# FPGA_0_V1_01.net
KiCad netlist of a schematic drawn in Altium Designer
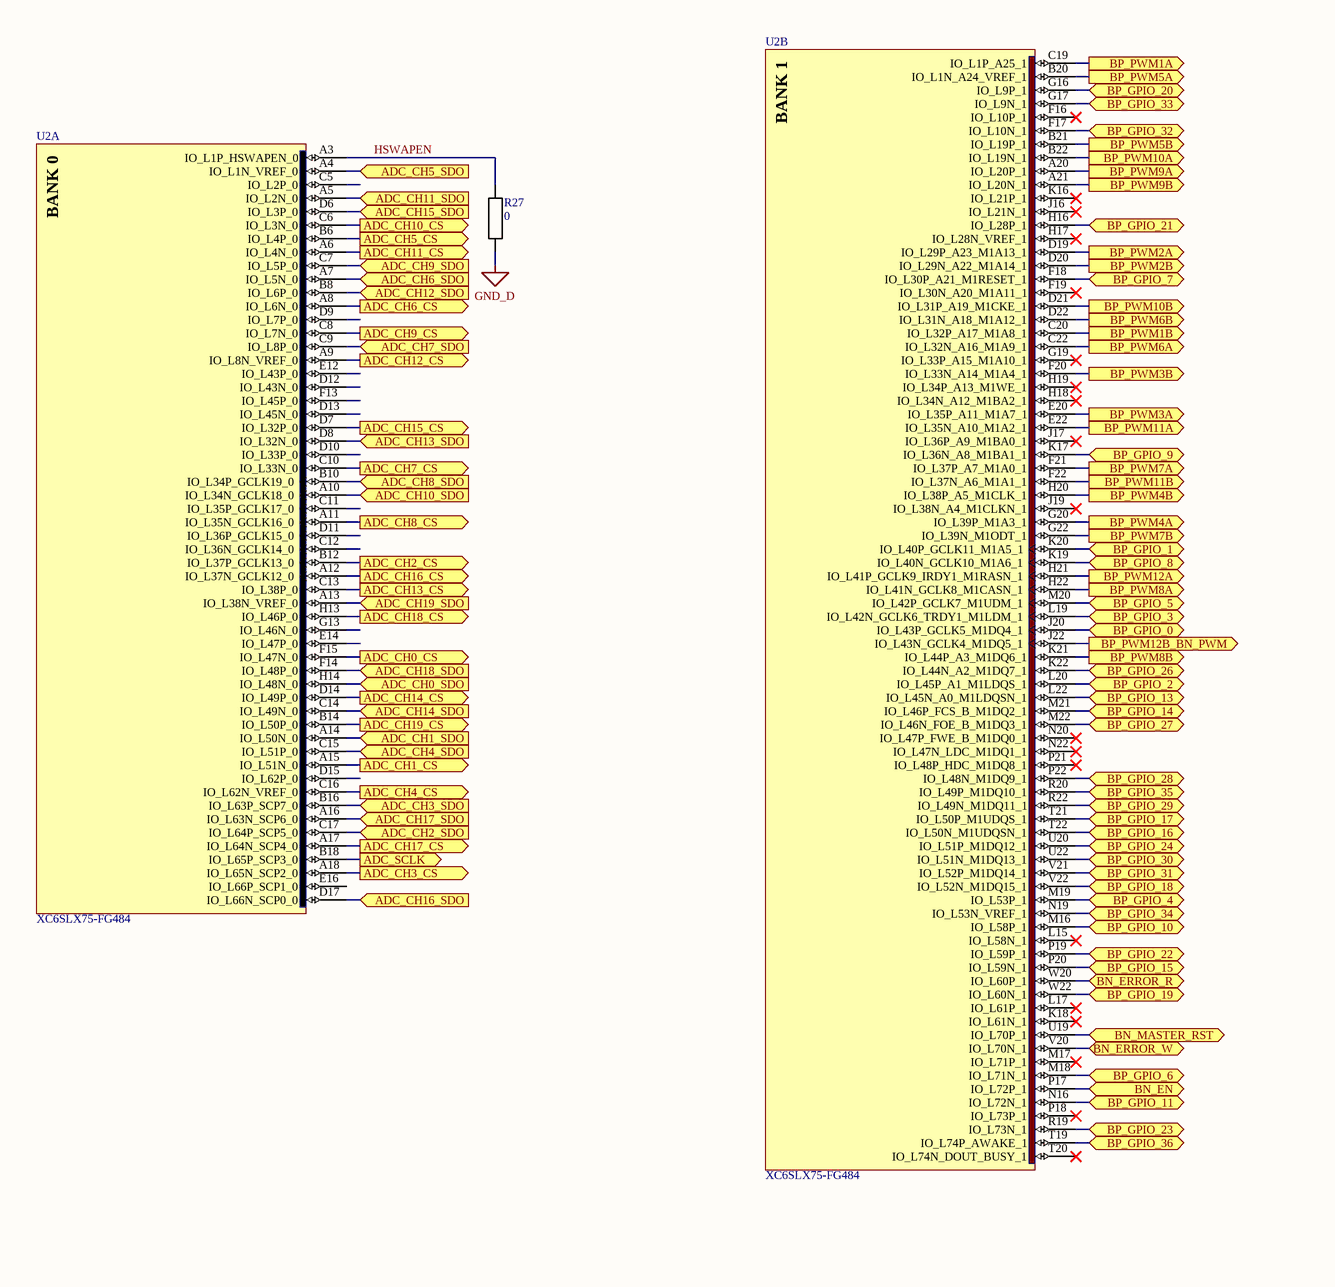
[diagram p0: FPGA_0_V1_01.SchDoc, left]
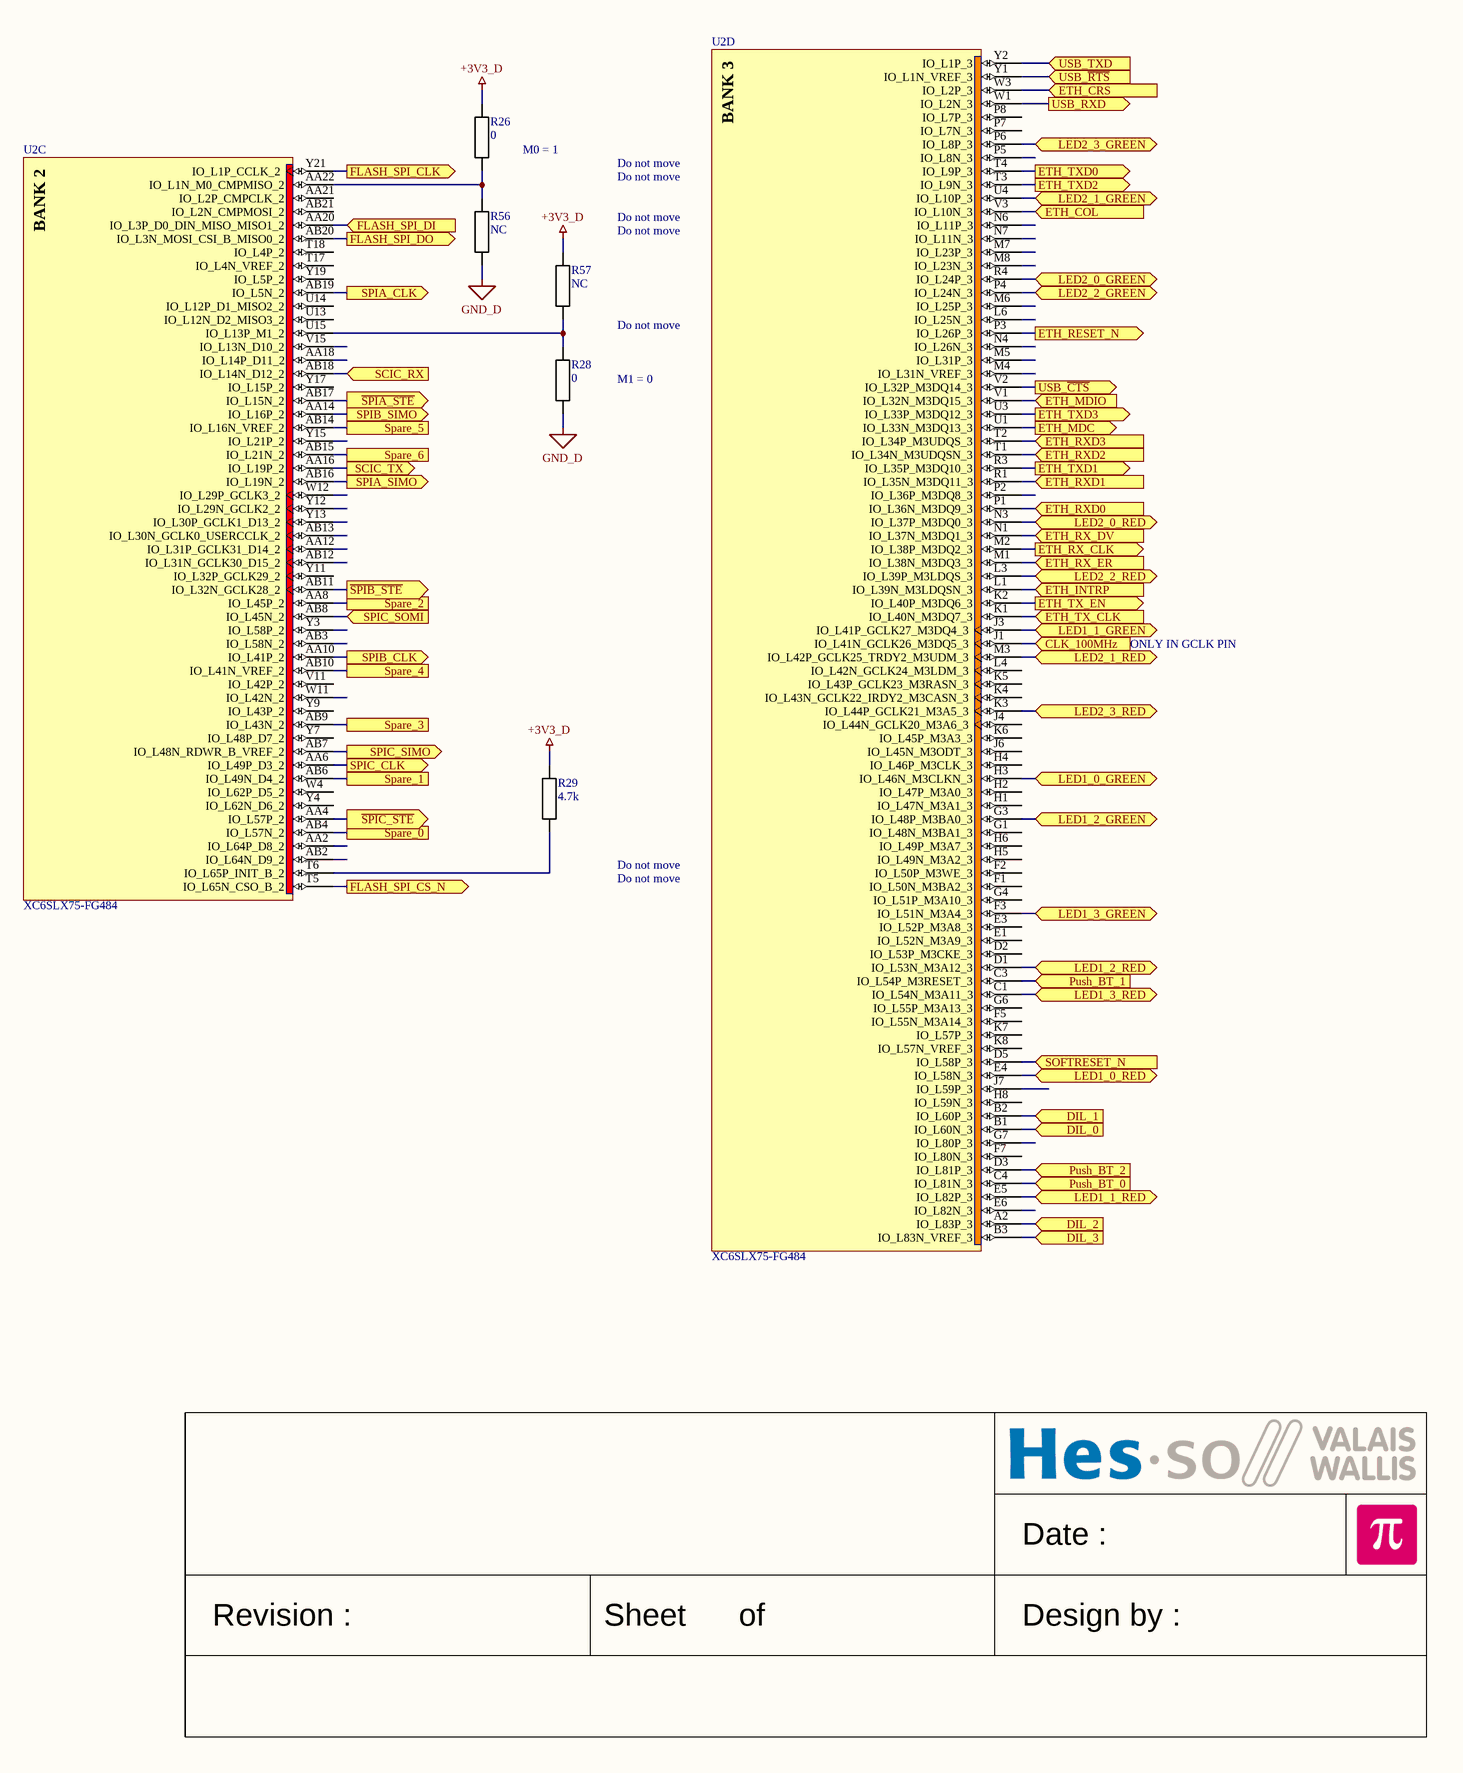
[diagram p1: FPGA_0_V1_01.SchDoc, right]

(export (version "E")
  (design (tool "Eeschema 10.0.6"))
  (components
    (comp (ref "R26")
      (value "0")
      (footprint "RESISTOR 2012 REFLOW")
      (description "Resistor 1% 50V 125mW 2012(0805)")
      (libsource (lib "Resistor") (part "Resistor"))
    )
    (comp (ref "R27")
      (value "0")
      (footprint "RESISTOR 2012 REFLOW")
      (description "Resistor 1% 50V 125mW 2012(0805)")
      (libsource (lib "Resistor") (part "Resistor"))
    )
    (comp (ref "R28")
      (value "0")
      (footprint "RESISTOR 2012 REFLOW")
      (description "Resistor 1% 50V 125mW 2012(0805)")
      (libsource (lib "Resistor") (part "Resistor"))
    )
    (comp (ref "R29")
      (value "4.7k")
      (footprint "RESISTOR 2012 REFLOW")
      (description "Resistor 1% 50V 125mW 2012(0805)")
      (libsource (lib "Resistor") (part "Resistor"))
    )
    (comp (ref "R56")
      (value "NC")
      (footprint "RESISTOR 2012 REFLOW")
      (description "Resistor 1% 50V 125mW 2012(0805)")
      (libsource (lib "Resistor") (part "Resistor"))
    )
    (comp (ref "R57")
      (value "NC")
      (footprint "RESISTOR 2012 REFLOW")
      (description "Resistor 1% 50V 125mW 2012(0805)")
      (libsource (lib "Resistor") (part "Resistor"))
    )
    (comp (ref "U2")
      (value "XC6SLX75-FG484")
      (footprint "BGA484 P1.0 C23X23 H2.2")
      (description "Spartan-6 LXT 1.2V FPGA, 268 User I/Os, 484-Ball Fine-Pitch BGA (1.0mm Pitch)")
      (libsource (lib "Processor") (part "XC6SLX75-FG484"))
    )
  )
  (nets
    (net (code "1") (name "+3V3_D") (class "Default")
      (node (ref "R26") (pin "2") (pinfunction "2_2") (pintype "passive"))
      (node (ref "R29") (pin "2") (pinfunction "2_2") (pintype "passive"))
      (node (ref "R57") (pin "2") (pinfunction "2_2") (pintype "passive"))
    )
    (net (code "2") (name "/ADC_CH0_CS") (class "Default")
      (node (ref "U2") (pin "F15") (pinfunction "IO_L47N_0_F15") (pintype "bidirectional"))
    )
    (net (code "3") (name "/ADC_CH0_SDO") (class "Default")
      (node (ref "U2") (pin "H14") (pinfunction "IO_L48N_0_H14") (pintype "bidirectional"))
    )
    (net (code "4") (name "/ADC_CH1_CS") (class "Default")
      (node (ref "U2") (pin "A15") (pinfunction "IO_L51N_0_A15") (pintype "bidirectional"))
    )
    (net (code "5") (name "/ADC_CH1_SDO") (class "Default")
      (node (ref "U2") (pin "A14") (pinfunction "IO_L50N_0_A14") (pintype "bidirectional"))
    )
    (net (code "6") (name "/ADC_CH2_CS") (class "Default")
      (node (ref "U2") (pin "B12") (pinfunction "IO_L37P_GCLK13_0_B12") (pintype "bidirectional"))
    )
    (net (code "7") (name "/ADC_CH2_SDO") (class "Default")
      (node (ref "U2") (pin "C17") (pinfunction "IO_L64P_SCP5_0_C17") (pintype "bidirectional"))
    )
    (net (code "8") (name "/ADC_CH3_CS") (class "Default")
      (node (ref "U2") (pin "A18") (pinfunction "IO_L65N_SCP2_0_A18") (pintype "bidirectional"))
    )
    (net (code "9") (name "/ADC_CH3_SDO") (class "Default")
      (node (ref "U2") (pin "B16") (pinfunction "IO_L63P_SCP7_0_B16") (pintype "bidirectional"))
    )
    (net (code "10") (name "/ADC_CH4_CS") (class "Default")
      (node (ref "U2") (pin "C16") (pinfunction "IO_L62N_VREF_0_C16") (pintype "bidirectional"))
    )
    (net (code "11") (name "/ADC_CH4_SDO") (class "Default")
      (node (ref "U2") (pin "C15") (pinfunction "IO_L51P_0_C15") (pintype "bidirectional"))
    )
    (net (code "12") (name "/ADC_CH5_CS") (class "Default")
      (node (ref "U2") (pin "B6") (pinfunction "IO_L4P_0_B6") (pintype "bidirectional"))
    )
    (net (code "13") (name "/ADC_CH5_SDO") (class "Default")
      (node (ref "U2") (pin "A4") (pinfunction "IO_L1N_VREF_0_A4") (pintype "bidirectional"))
    )
    (net (code "14") (name "/ADC_CH6_CS") (class "Default")
      (node (ref "U2") (pin "A8") (pinfunction "IO_L6N_0_A8") (pintype "bidirectional"))
    )
    (net (code "15") (name "/ADC_CH6_SDO") (class "Default")
      (node (ref "U2") (pin "A7") (pinfunction "IO_L5N_0_A7") (pintype "bidirectional"))
    )
    (net (code "16") (name "/ADC_CH7_CS") (class "Default")
      (node (ref "U2") (pin "C10") (pinfunction "IO_L33N_0_C10") (pintype "bidirectional"))
    )
    (net (code "17") (name "/ADC_CH7_SDO") (class "Default")
      (node (ref "U2") (pin "C9") (pinfunction "IO_L8P_0_C9") (pintype "bidirectional"))
    )
    (net (code "18") (name "/ADC_CH8_CS") (class "Default")
      (node (ref "U2") (pin "A11") (pinfunction "IO_L35N_GCLK16_0_A11") (pintype "bidirectional"))
    )
    (net (code "19") (name "/ADC_CH8_SDO") (class "Default")
      (node (ref "U2") (pin "B10") (pinfunction "IO_L34P_GCLK19_0_B10") (pintype "bidirectional"))
    )
    (net (code "20") (name "/ADC_CH9_CS") (class "Default")
      (node (ref "U2") (pin "C8") (pinfunction "IO_L7N_0_C8") (pintype "bidirectional"))
    )
    (net (code "21") (name "/ADC_CH9_SDO") (class "Default")
      (node (ref "U2") (pin "C7") (pinfunction "IO_L5P_0_C7") (pintype "bidirectional"))
    )
    (net (code "22") (name "/ADC_CH10_CS") (class "Default")
      (node (ref "U2") (pin "C6") (pinfunction "IO_L3N_0_C6") (pintype "bidirectional"))
    )
    (net (code "23") (name "/ADC_CH10_SDO") (class "Default")
      (node (ref "U2") (pin "A10") (pinfunction "IO_L34N_GCLK18_0_A10") (pintype "bidirectional"))
    )
    (net (code "24") (name "/ADC_CH11_CS") (class "Default")
      (node (ref "U2") (pin "A6") (pinfunction "IO_L4N_0_A6") (pintype "bidirectional"))
    )
    (net (code "25") (name "/ADC_CH11_SDO") (class "Default")
      (node (ref "U2") (pin "A5") (pinfunction "IO_L2N_0_A5") (pintype "bidirectional"))
    )
    (net (code "26") (name "/ADC_CH12_CS") (class "Default")
      (node (ref "U2") (pin "A9") (pinfunction "IO_L8N_VREF_0_A9") (pintype "bidirectional"))
    )
    (net (code "27") (name "/ADC_CH12_SDO") (class "Default")
      (node (ref "U2") (pin "B8") (pinfunction "IO_L6P_0_B8") (pintype "bidirectional"))
    )
    (net (code "28") (name "/ADC_CH13_CS") (class "Default")
      (node (ref "U2") (pin "C13") (pinfunction "IO_L38P_0_C13") (pintype "bidirectional"))
    )
    (net (code "29") (name "/ADC_CH13_SDO") (class "Default")
      (node (ref "U2") (pin "D8") (pinfunction "IO_L32N_0_D8") (pintype "bidirectional"))
    )
    (net (code "30") (name "/ADC_CH14_CS") (class "Default")
      (node (ref "U2") (pin "D14") (pinfunction "IO_L49P_0_D14") (pintype "bidirectional"))
    )
    (net (code "31") (name "/ADC_CH14_SDO") (class "Default")
      (node (ref "U2") (pin "C14") (pinfunction "IO_L49N_0_C14") (pintype "bidirectional"))
    )
    (net (code "32") (name "/ADC_CH15_CS") (class "Default")
      (node (ref "U2") (pin "D7") (pinfunction "IO_L32P_0_D7") (pintype "bidirectional"))
    )
    (net (code "33") (name "/ADC_CH15_SDO") (class "Default")
      (node (ref "U2") (pin "D6") (pinfunction "IO_L3P_0_D6") (pintype "bidirectional"))
    )
    (net (code "34") (name "/ADC_CH16_CS") (class "Default")
      (node (ref "U2") (pin "A12") (pinfunction "IO_L37N_GCLK12_0_A12") (pintype "bidirectional"))
    )
    (net (code "35") (name "/ADC_CH16_SDO") (class "Default")
      (node (ref "U2") (pin "D17") (pinfunction "IO_L66N_SCP0_0_D17") (pintype "bidirectional"))
    )
    (net (code "36") (name "/ADC_CH17_CS") (class "Default")
      (node (ref "U2") (pin "A17") (pinfunction "IO_L64N_SCP4_0_A17") (pintype "bidirectional"))
    )
    (net (code "37") (name "/ADC_CH17_SDO") (class "Default")
      (node (ref "U2") (pin "A16") (pinfunction "IO_L63N_SCP6_0_A16") (pintype "bidirectional"))
    )
    (net (code "38") (name "/ADC_CH18_CS") (class "Default")
      (node (ref "U2") (pin "H13") (pinfunction "IO_L46P_0_H13") (pintype "bidirectional"))
    )
    (net (code "39") (name "/ADC_CH18_SDO") (class "Default")
      (node (ref "U2") (pin "F14") (pinfunction "IO_L48P_0_F14") (pintype "bidirectional"))
    )
    (net (code "40") (name "/ADC_CH19_CS") (class "Default")
      (node (ref "U2") (pin "B14") (pinfunction "IO_L50P_0_B14") (pintype "bidirectional"))
    )
    (net (code "41") (name "/ADC_CH19_SDO") (class "Default")
      (node (ref "U2") (pin "A13") (pinfunction "IO_L38N_VREF_0_A13") (pintype "bidirectional"))
    )
    (net (code "42") (name "/ADC_SCLK") (class "Default")
      (node (ref "U2") (pin "B18") (pinfunction "IO_L65P_SCP3_0_B18") (pintype "bidirectional"))
    )
    (net (code "43") (name "/BN_EN") (class "Default")
      (node (ref "U2") (pin "P17") (pinfunction "IO_L72P_1_P17") (pintype "bidirectional"))
    )
    (net (code "44") (name "/BN_ERROR_R") (class "Default")
      (node (ref "U2") (pin "W20") (pinfunction "IO_L60P_1_W20") (pintype "bidirectional"))
    )
    (net (code "45") (name "/BN_ERROR_W") (class "Default")
      (node (ref "U2") (pin "V20") (pinfunction "IO_L70N_1_V20") (pintype "bidirectional"))
    )
    (net (code "46") (name "/BN_MASTER_RST") (class "Default")
      (node (ref "U2") (pin "U19") (pinfunction "IO_L70P_1_U19") (pintype "bidirectional"))
    )
    (net (code "47") (name "/BP_GPIO_0") (class "Default")
      (node (ref "U2") (pin "J20") (pinfunction "IO_L43P_GCLK5_M1DQ4_1_J20") (pintype "bidirectional"))
    )
    (net (code "48") (name "/BP_GPIO_1") (class "Default")
      (node (ref "U2") (pin "K20") (pinfunction "IO_L40P_GCLK11_M1A5_1_K20") (pintype "bidirectional"))
    )
    (net (code "49") (name "/BP_GPIO_2") (class "Default")
      (node (ref "U2") (pin "L20") (pinfunction "IO_L45P_A1_M1LDQS_1_L20") (pintype "bidirectional"))
    )
    (net (code "50") (name "/BP_GPIO_3") (class "Default")
      (node (ref "U2") (pin "L19") (pinfunction "IO_L42N_GCLK6_TRDY1_M1LDM_1_L19") (pintype "bidirectional"))
    )
    (net (code "51") (name "/BP_GPIO_4") (class "Default")
      (node (ref "U2") (pin "M19") (pinfunction "IO_L53P_1_M19") (pintype "bidirectional"))
    )
    (net (code "52") (name "/BP_GPIO_5") (class "Default")
      (node (ref "U2") (pin "M20") (pinfunction "IO_L42P_GCLK7_M1UDM_1_M20") (pintype "bidirectional"))
    )
    (net (code "53") (name "/BP_GPIO_6") (class "Default")
      (node (ref "U2") (pin "M18") (pinfunction "IO_L71N_1_M18") (pintype "bidirectional"))
    )
    (net (code "54") (name "/BP_GPIO_7") (class "Default")
      (node (ref "U2") (pin "F18") (pinfunction "IO_L30P_A21_M1RESET_1_F18") (pintype "bidirectional"))
    )
    (net (code "55") (name "/BP_GPIO_8") (class "Default")
      (node (ref "U2") (pin "K19") (pinfunction "IO_L40N_GCLK10_M1A6_1_K19") (pintype "bidirectional"))
    )
    (net (code "56") (name "/BP_GPIO_9") (class "Default")
      (node (ref "U2") (pin "K17") (pinfunction "IO_L36N_A8_M1BA1_1_K17") (pintype "bidirectional"))
    )
    (net (code "57") (name "/BP_GPIO_10") (class "Default")
      (node (ref "U2") (pin "M16") (pinfunction "IO_L58P_1_M16") (pintype "bidirectional"))
    )
    (net (code "58") (name "/BP_GPIO_11") (class "Default")
      (node (ref "U2") (pin "N16") (pinfunction "IO_L72N_1_N16") (pintype "bidirectional"))
    )
    (net (code "59") (name "/BP_GPIO_13") (class "Default")
      (node (ref "U2") (pin "L22") (pinfunction "IO_L45N_A0_M1LDQSN_1_L22") (pintype "bidirectional"))
    )
    (net (code "60") (name "/BP_GPIO_14") (class "Default")
      (node (ref "U2") (pin "M21") (pinfunction "IO_L46P_FCS_B_M1DQ2_1_M21") (pintype "bidirectional"))
    )
    (net (code "61") (name "/BP_GPIO_15") (class "Default")
      (node (ref "U2") (pin "P20") (pinfunction "IO_L59N_1_P20") (pintype "bidirectional"))
    )
    (net (code "62") (name "/BP_GPIO_16") (class "Default")
      (node (ref "U2") (pin "T22") (pinfunction "IO_L50N_M1UDQSN_1_T22") (pintype "bidirectional"))
    )
    (net (code "63") (name "/BP_GPIO_17") (class "Default")
      (node (ref "U2") (pin "T21") (pinfunction "IO_L50P_M1UDQS_1_T21") (pintype "bidirectional"))
    )
    (net (code "64") (name "/BP_GPIO_18") (class "Default")
      (node (ref "U2") (pin "V22") (pinfunction "IO_L52N_M1DQ15_1_V22") (pintype "bidirectional"))
    )
    (net (code "65") (name "/BP_GPIO_19") (class "Default")
      (node (ref "U2") (pin "W22") (pinfunction "IO_L60N_1_W22") (pintype "bidirectional"))
    )
    (net (code "66") (name "/BP_GPIO_20") (class "Default")
      (node (ref "U2") (pin "G16") (pinfunction "IO_L9P_1_G16") (pintype "bidirectional"))
    )
    (net (code "67") (name "/BP_GPIO_21") (class "Default")
      (node (ref "U2") (pin "H16") (pinfunction "IO_L28P_1_H16") (pintype "bidirectional"))
    )
    (net (code "68") (name "/BP_GPIO_22") (class "Default")
      (node (ref "U2") (pin "P19") (pinfunction "IO_L59P_1_P19") (pintype "bidirectional"))
    )
    (net (code "69") (name "/BP_GPIO_23") (class "Default")
      (node (ref "U2") (pin "R19") (pinfunction "IO_L73N_1_R19") (pintype "bidirectional"))
    )
    (net (code "70") (name "/BP_GPIO_24") (class "Default")
      (node (ref "U2") (pin "U20") (pinfunction "IO_L51P_M1DQ12_1_U20") (pintype "bidirectional"))
    )
    (net (code "71") (name "/BP_GPIO_26") (class "Default")
      (node (ref "U2") (pin "K22") (pinfunction "IO_L44N_A2_M1DQ7_1_K22") (pintype "bidirectional"))
    )
    (net (code "72") (name "/BP_GPIO_27") (class "Default")
      (node (ref "U2") (pin "M22") (pinfunction "IO_L46N_FOE_B_M1DQ3_1_M22") (pintype "bidirectional"))
    )
    (net (code "73") (name "/BP_GPIO_28") (class "Default")
      (node (ref "U2") (pin "P22") (pinfunction "IO_L48N_M1DQ9_1_P22") (pintype "bidirectional"))
    )
    (net (code "74") (name "/BP_GPIO_29") (class "Default")
      (node (ref "U2") (pin "R22") (pinfunction "IO_L49N_M1DQ11_1_R22") (pintype "bidirectional"))
    )
    (net (code "75") (name "/BP_GPIO_30") (class "Default")
      (node (ref "U2") (pin "U22") (pinfunction "IO_L51N_M1DQ13_1_U22") (pintype "bidirectional"))
    )
    (net (code "76") (name "/BP_GPIO_31") (class "Default")
      (node (ref "U2") (pin "V21") (pinfunction "IO_L52P_M1DQ14_1_V21") (pintype "bidirectional"))
    )
    (net (code "77") (name "/BP_GPIO_32") (class "Default")
      (node (ref "U2") (pin "F17") (pinfunction "IO_L10N_1_F17") (pintype "bidirectional"))
    )
    (net (code "78") (name "/BP_GPIO_33") (class "Default")
      (node (ref "U2") (pin "G17") (pinfunction "IO_L9N_1_G17") (pintype "bidirectional"))
    )
    (net (code "79") (name "/BP_GPIO_34") (class "Default")
      (node (ref "U2") (pin "N19") (pinfunction "IO_L53N_VREF_1_N19") (pintype "bidirectional"))
    )
    (net (code "80") (name "/BP_GPIO_35") (class "Default")
      (node (ref "U2") (pin "R20") (pinfunction "IO_L49P_M1DQ10_1_R20") (pintype "bidirectional"))
    )
    (net (code "81") (name "/BP_GPIO_36") (class "Default")
      (node (ref "U2") (pin "T19") (pinfunction "IO_L74P_AWAKE_1_T19") (pintype "bidirectional"))
    )
    (net (code "82") (name "/BP_PWM1A") (class "Default")
      (node (ref "U2") (pin "C19") (pinfunction "IO_L1P_A25_1_C19") (pintype "bidirectional"))
    )
    (net (code "83") (name "/BP_PWM1B") (class "Default")
      (node (ref "U2") (pin "C20") (pinfunction "IO_L32P_A17_M1A8_1_C20") (pintype "bidirectional"))
    )
    (net (code "84") (name "/BP_PWM2A") (class "Default")
      (node (ref "U2") (pin "D19") (pinfunction "IO_L29P_A23_M1A13_1_D19") (pintype "bidirectional"))
    )
    (net (code "85") (name "/BP_PWM2B") (class "Default")
      (node (ref "U2") (pin "D20") (pinfunction "IO_L29N_A22_M1A14_1_D20") (pintype "bidirectional"))
    )
    (net (code "86") (name "/BP_PWM3A") (class "Default")
      (node (ref "U2") (pin "E20") (pinfunction "IO_L35P_A11_M1A7_1_E20") (pintype "bidirectional"))
    )
    (net (code "87") (name "/BP_PWM3B") (class "Default")
      (node (ref "U2") (pin "F20") (pinfunction "IO_L33N_A14_M1A4_1_F20") (pintype "bidirectional"))
    )
    (net (code "88") (name "/BP_PWM4A") (class "Default")
      (node (ref "U2") (pin "G20") (pinfunction "IO_L39P_M1A3_1_G20") (pintype "bidirectional"))
    )
    (net (code "89") (name "/BP_PWM4B") (class "Default")
      (node (ref "U2") (pin "H20") (pinfunction "IO_L38P_A5_M1CLK_1_H20") (pintype "bidirectional"))
    )
    (net (code "90") (name "/BP_PWM5A") (class "Default")
      (node (ref "U2") (pin "B20") (pinfunction "IO_L1N_A24_VREF_1_B20") (pintype "bidirectional"))
    )
    (net (code "91") (name "/BP_PWM5B") (class "Default")
      (node (ref "U2") (pin "B21") (pinfunction "IO_L19P_1_B21") (pintype "bidirectional"))
    )
    (net (code "92") (name "/BP_PWM6A") (class "Default")
      (node (ref "U2") (pin "C22") (pinfunction "IO_L32N_A16_M1A9_1_C22") (pintype "bidirectional"))
    )
    (net (code "93") (name "/BP_PWM6B") (class "Default")
      (node (ref "U2") (pin "D22") (pinfunction "IO_L31N_A18_M1A12_1_D22") (pintype "bidirectional"))
    )
    (net (code "94") (name "/BP_PWM7A") (class "Default")
      (node (ref "U2") (pin "F21") (pinfunction "IO_L37P_A7_M1A0_1_F21") (pintype "bidirectional"))
    )
    (net (code "95") (name "/BP_PWM7B") (class "Default")
      (node (ref "U2") (pin "G22") (pinfunction "IO_L39N_M1ODT_1_G22") (pintype "bidirectional"))
    )
    (net (code "96") (name "/BP_PWM8A") (class "Default")
      (node (ref "U2") (pin "H22") (pinfunction "IO_L41N_GCLK8_M1CASN_1_H22") (pintype "bidirectional"))
    )
    (net (code "97") (name "/BP_PWM8B") (class "Default")
      (node (ref "U2") (pin "K21") (pinfunction "IO_L44P_A3_M1DQ6_1_K21") (pintype "bidirectional"))
    )
    (net (code "98") (name "/BP_PWM9A") (class "Default")
      (node (ref "U2") (pin "A20") (pinfunction "IO_L20P_1_A20") (pintype "bidirectional"))
    )
    (net (code "99") (name "/BP_PWM9B") (class "Default")
      (node (ref "U2") (pin "A21") (pinfunction "IO_L20N_1_A21") (pintype "bidirectional"))
    )
    (net (code "100") (name "/BP_PWM10A") (class "Default")
      (node (ref "U2") (pin "B22") (pinfunction "IO_L19N_1_B22") (pintype "bidirectional"))
    )
    (net (code "101") (name "/BP_PWM10B") (class "Default")
      (node (ref "U2") (pin "D21") (pinfunction "IO_L31P_A19_M1CKE_1_D21") (pintype "bidirectional"))
    )
    (net (code "102") (name "/BP_PWM11A") (class "Default")
      (node (ref "U2") (pin "E22") (pinfunction "IO_L35N_A10_M1A2_1_E22") (pintype "bidirectional"))
    )
    (net (code "103") (name "/BP_PWM11B") (class "Default")
      (node (ref "U2") (pin "F22") (pinfunction "IO_L37N_A6_M1A1_1_F22") (pintype "bidirectional"))
    )
    (net (code "104") (name "/BP_PWM12A") (class "Default")
      (node (ref "U2") (pin "H21") (pinfunction "IO_L41P_GCLK9_IRDY1_M1RASN_1_H21") (pintype "bidirectional"))
    )
    (net (code "105") (name "/BP_PWM12B_BN_PWM") (class "Default")
      (node (ref "U2") (pin "J22") (pinfunction "IO_L43N_GCLK4_M1DQ5_1_J22") (pintype "bidirectional"))
    )
    (net (code "106") (name "/CLK_100MHz") (class "Default")
      (node (ref "U2") (pin "J1") (pinfunction "IO_L41N_GCLK26_M3DQ5_3_J1") (pintype "bidirectional"))
    )
    (net (code "107") (name "/DIL_0") (class "Default")
      (node (ref "U2") (pin "B1") (pinfunction "IO_L60N_3_B1") (pintype "bidirectional"))
    )
    (net (code "108") (name "/DIL_1") (class "Default")
      (node (ref "U2") (pin "B2") (pinfunction "IO_L60P_3_B2") (pintype "bidirectional"))
    )
    (net (code "109") (name "/DIL_2") (class "Default")
      (node (ref "U2") (pin "A2") (pinfunction "IO_L83P_3_A2") (pintype "bidirectional"))
    )
    (net (code "110") (name "/DIL_3") (class "Default")
      (node (ref "U2") (pin "B3") (pinfunction "IO_L83N_VREF_3_B3") (pintype "bidirectional"))
    )
    (net (code "111") (name "/ETH_COL") (class "Default")
      (node (ref "U2") (pin "V3") (pinfunction "IO_L10N_3_V3") (pintype "bidirectional"))
    )
    (net (code "112") (name "/ETH_CRS") (class "Default")
      (node (ref "U2") (pin "W3") (pinfunction "IO_L2P_3_W3") (pintype "bidirectional"))
    )
    (net (code "113") (name "/ETH_INTRP") (class "Default")
      (node (ref "U2") (pin "L1") (pinfunction "IO_L39N_M3LDQSN_3_L1") (pintype "bidirectional"))
    )
    (net (code "114") (name "/ETH_MDC") (class "Default")
      (node (ref "U2") (pin "U1") (pinfunction "IO_L33N_M3DQ13_3_U1") (pintype "bidirectional"))
    )
    (net (code "115") (name "/ETH_MDIO") (class "Default")
      (node (ref "U2") (pin "V1") (pinfunction "IO_L32N_M3DQ15_3_V1") (pintype "bidirectional"))
    )
    (net (code "116") (name "/ETH_RESET_N") (class "Default")
      (node (ref "U2") (pin "P3") (pinfunction "IO_L26P_3_P3") (pintype "bidirectional"))
    )
    (net (code "117") (name "/ETH_RXD0") (class "Default")
      (node (ref "U2") (pin "P1") (pinfunction "IO_L36N_M3DQ9_3_P1") (pintype "bidirectional"))
    )
    (net (code "118") (name "/ETH_RXD1") (class "Default")
      (node (ref "U2") (pin "R1") (pinfunction "IO_L35N_M3DQ11_3_R1") (pintype "bidirectional"))
    )
    (net (code "119") (name "/ETH_RXD2") (class "Default")
      (node (ref "U2") (pin "T1") (pinfunction "IO_L34N_M3UDQSN_3_T1") (pintype "bidirectional"))
    )
    (net (code "120") (name "/ETH_RXD3") (class "Default")
      (node (ref "U2") (pin "T2") (pinfunction "IO_L34P_M3UDQS_3_T2") (pintype "bidirectional"))
    )
    (net (code "121") (name "/ETH_RX_CLK") (class "Default")
      (node (ref "U2") (pin "M2") (pinfunction "IO_L38P_M3DQ2_3_M2") (pintype "bidirectional"))
    )
    (net (code "122") (name "/ETH_RX_DV") (class "Default")
      (node (ref "U2") (pin "N1") (pinfunction "IO_L37N_M3DQ1_3_N1") (pintype "bidirectional"))
    )
    (net (code "123") (name "/ETH_RX_ER") (class "Default")
      (node (ref "U2") (pin "M1") (pinfunction "IO_L38N_M3DQ3_3_M1") (pintype "bidirectional"))
    )
    (net (code "124") (name "/ETH_TXD0") (class "Default")
      (node (ref "U2") (pin "T4") (pinfunction "IO_L9P_3_T4") (pintype "bidirectional"))
    )
    (net (code "125") (name "/ETH_TXD1") (class "Default")
      (node (ref "U2") (pin "R3") (pinfunction "IO_L35P_M3DQ10_3_R3") (pintype "bidirectional"))
    )
    (net (code "126") (name "/ETH_TXD2") (class "Default")
      (node (ref "U2") (pin "T3") (pinfunction "IO_L9N_3_T3") (pintype "bidirectional"))
    )
    (net (code "127") (name "/ETH_TXD3") (class "Default")
      (node (ref "U2") (pin "U3") (pinfunction "IO_L33P_M3DQ12_3_U3") (pintype "bidirectional"))
    )
    (net (code "128") (name "/ETH_TX_CLK") (class "Default")
      (node (ref "U2") (pin "K1") (pinfunction "IO_L40N_M3DQ7_3_K1") (pintype "bidirectional"))
    )
    (net (code "129") (name "/ETH_TX_EN") (class "Default")
      (node (ref "U2") (pin "K2") (pinfunction "IO_L40P_M3DQ6_3_K2") (pintype "bidirectional"))
    )
    (net (code "130") (name "/FLASH_SPI_CLK") (class "Default")
      (node (ref "U2") (pin "Y21") (pinfunction "IO_L1P_CCLK_2_Y21") (pintype "bidirectional"))
    )
    (net (code "131") (name "/FLASH_SPI_CS_N") (class "Default")
      (node (ref "U2") (pin "T5") (pinfunction "IO_L65N_CSO_B_2_T5") (pintype "bidirectional"))
    )
    (net (code "132") (name "/FLASH_SPI_DI") (class "Default")
      (node (ref "U2") (pin "AA20") (pinfunction "IO_L3P_D0_DIN_MISO_MISO1_2_AA20") (pintype "bidirectional"))
    )
    (net (code "133") (name "/FLASH_SPI_DO") (class "Default")
      (node (ref "U2") (pin "AB20") (pinfunction "IO_L3N_MOSI_CSI_B_MISO0_2_AB20") (pintype "bidirectional"))
    )
    (net (code "134") (name "/HSWAPEN") (class "Default")
      (node (ref "R27") (pin "2") (pinfunction "2_2") (pintype "passive"))
      (node (ref "U2") (pin "A3") (pinfunction "IO_L1P_HSWAPEN_0_A3") (pintype "bidirectional"))
    )
    (net (code "135") (name "/LED1_0_GREEN") (class "Default")
      (node (ref "U2") (pin "H3") (pinfunction "IO_L46N_M3CLKN_3_H3") (pintype "bidirectional"))
    )
    (net (code "136") (name "/LED1_0_RED") (class "Default")
      (node (ref "U2") (pin "E4") (pinfunction "IO_L58N_3_E4") (pintype "bidirectional"))
    )
    (net (code "137") (name "/LED1_1_GREEN") (class "Default")
      (node (ref "U2") (pin "J3") (pinfunction "IO_L41P_GCLK27_M3DQ4_3_J3") (pintype "bidirectional"))
    )
    (net (code "138") (name "/LED1_1_RED") (class "Default")
      (node (ref "U2") (pin "E5") (pinfunction "IO_L82P_3_E5") (pintype "bidirectional"))
    )
    (net (code "139") (name "/LED1_2_GREEN") (class "Default")
      (node (ref "U2") (pin "G3") (pinfunction "IO_L48P_M3BA0_3_G3") (pintype "bidirectional"))
    )
    (net (code "140") (name "/LED1_2_RED") (class "Default")
      (node (ref "U2") (pin "D1") (pinfunction "IO_L53N_M3A12_3_D1") (pintype "bidirectional"))
    )
    (net (code "141") (name "/LED1_3_GREEN") (class "Default")
      (node (ref "U2") (pin "F3") (pinfunction "IO_L51N_M3A4_3_F3") (pintype "bidirectional"))
    )
    (net (code "142") (name "/LED1_3_RED") (class "Default")
      (node (ref "U2") (pin "C1") (pinfunction "IO_L54N_M3A11_3_C1") (pintype "bidirectional"))
    )
    (net (code "143") (name "/LED2_0_GREEN") (class "Default")
      (node (ref "U2") (pin "R4") (pinfunction "IO_L24P_3_R4") (pintype "bidirectional"))
    )
    (net (code "144") (name "/LED2_0_RED") (class "Default")
      (node (ref "U2") (pin "N3") (pinfunction "IO_L37P_M3DQ0_3_N3") (pintype "bidirectional"))
    )
    (net (code "145") (name "/LED2_1_GREEN") (class "Default")
      (node (ref "U2") (pin "U4") (pinfunction "IO_L10P_3_U4") (pintype "bidirectional"))
    )
    (net (code "146") (name "/LED2_1_RED") (class "Default")
      (node (ref "U2") (pin "M3") (pinfunction "IO_L42P_GCLK25_TRDY2_M3UDM_3_M3") (pintype "bidirectional"))
    )
    (net (code "147") (name "/LED2_2_GREEN") (class "Default")
      (node (ref "U2") (pin "P4") (pinfunction "IO_L24N_3_P4") (pintype "bidirectional"))
    )
    (net (code "148") (name "/LED2_2_RED") (class "Default")
      (node (ref "U2") (pin "L3") (pinfunction "IO_L39P_M3LDQS_3_L3") (pintype "bidirectional"))
    )
    (net (code "149") (name "/LED2_3_GREEN") (class "Default")
      (node (ref "U2") (pin "P6") (pinfunction "IO_L8P_3_P6") (pintype "bidirectional"))
    )
    (net (code "150") (name "/LED2_3_RED") (class "Default")
      (node (ref "U2") (pin "K3") (pinfunction "IO_L44P_GCLK21_M3A5_3_K3") (pintype "bidirectional"))
    )
    (net (code "151") (name "/Push_BT_0") (class "Default")
      (node (ref "U2") (pin "C4") (pinfunction "IO_L81N_3_C4") (pintype "bidirectional"))
    )
    (net (code "152") (name "/Push_BT_1") (class "Default")
      (node (ref "U2") (pin "C3") (pinfunction "IO_L54P_M3RESET_3_C3") (pintype "bidirectional"))
    )
    (net (code "153") (name "/Push_BT_2") (class "Default")
      (node (ref "U2") (pin "D3") (pinfunction "IO_L81P_3_D3") (pintype "bidirectional"))
    )
    (net (code "154") (name "/SCIC_RX") (class "Default")
      (node (ref "U2") (pin "AB18") (pinfunction "IO_L14N_D12_2_AB18") (pintype "bidirectional"))
    )
    (net (code "155") (name "/SCIC_TX") (class "Default")
      (node (ref "U2") (pin "AA16") (pinfunction "IO_L19P_2_AA16") (pintype "bidirectional"))
    )
    (net (code "156") (name "/SOFTRESET_N") (class "Default")
      (node (ref "U2") (pin "D5") (pinfunction "IO_L58P_3_D5") (pintype "bidirectional"))
    )
    (net (code "157") (name "/SPIA_CLK") (class "Default")
      (node (ref "U2") (pin "AB19") (pinfunction "IO_L5N_2_AB19") (pintype "bidirectional"))
    )
    (net (code "158") (name "/SPIA_SIMO") (class "Default")
      (node (ref "U2") (pin "AB16") (pinfunction "IO_L19N_2_AB16") (pintype "bidirectional"))
    )
    (net (code "159") (name "/SPIB_CLK") (class "Default")
      (node (ref "U2") (pin "AA10") (pinfunction "IO_L41P_2_AA10") (pintype "bidirectional"))
    )
    (net (code "160") (name "/SPIB_SIMO") (class "Default")
      (node (ref "U2") (pin "AA14") (pinfunction "IO_L16P_2_AA14") (pintype "bidirectional"))
    )
    (net (code "161") (name "/SPIC_CLK") (class "Default")
      (node (ref "U2") (pin "AA6") (pinfunction "IO_L49P_D3_2_AA6") (pintype "bidirectional"))
    )
    (net (code "162") (name "/SPIC_SIMO") (class "Default")
      (node (ref "U2") (pin "AB7") (pinfunction "IO_L48N_RDWR_B_VREF_2_AB7") (pintype "bidirectional"))
    )
    (net (code "163") (name "/SPIC_SOMI") (class "Default")
      (node (ref "U2") (pin "AB8") (pinfunction "IO_L45N_2_AB8") (pintype "bidirectional"))
    )
    (net (code "164") (name "/Spare_0") (class "Default")
      (node (ref "U2") (pin "AB4") (pinfunction "IO_L57N_2_AB4") (pintype "bidirectional"))
    )
    (net (code "165") (name "/Spare_1") (class "Default")
      (node (ref "U2") (pin "AB6") (pinfunction "IO_L49N_D4_2_AB6") (pintype "bidirectional"))
    )
    (net (code "166") (name "/Spare_2") (class "Default")
      (node (ref "U2") (pin "AA8") (pinfunction "IO_L45P_2_AA8") (pintype "bidirectional"))
    )
    (net (code "167") (name "/Spare_3") (class "Default")
      (node (ref "U2") (pin "AB9") (pinfunction "IO_L43N_2_AB9") (pintype "bidirectional"))
    )
    (net (code "168") (name "/Spare_4") (class "Default")
      (node (ref "U2") (pin "AB10") (pinfunction "IO_L41N_VREF_2_AB10") (pintype "bidirectional"))
    )
    (net (code "169") (name "/Spare_5") (class "Default")
      (node (ref "U2") (pin "AB14") (pinfunction "IO_L16N_VREF_2_AB14") (pintype "bidirectional"))
    )
    (net (code "170") (name "/Spare_6") (class "Default")
      (node (ref "U2") (pin "AB15") (pinfunction "IO_L21N_2_AB15") (pintype "bidirectional"))
    )
    (net (code "171") (name "/USB_RXD") (class "Default")
      (node (ref "U2") (pin "W1") (pinfunction "IO_L2N_3_W1") (pintype "bidirectional"))
    )
    (net (code "172") (name "/USB_TXD") (class "Default")
      (node (ref "U2") (pin "Y2") (pinfunction "IO_L1P_3_Y2") (pintype "bidirectional"))
    )
    (net (code "173") (name "/USB_~{CTS}") (class "Default")
      (node (ref "U2") (pin "V2") (pinfunction "IO_L32P_M3DQ14_3_V2") (pintype "bidirectional"))
    )
    (net (code "174") (name "/USB_~{RTS}") (class "Default")
      (node (ref "U2") (pin "Y1") (pinfunction "IO_L1N_VREF_3_Y1") (pintype "bidirectional"))
    )
    (net (code "175") (name "/~{SPIA_STE}") (class "Default")
      (node (ref "U2") (pin "AB17") (pinfunction "IO_L15N_2_AB17") (pintype "bidirectional"))
    )
    (net (code "176") (name "/~{SPIB_STE}") (class "Default")
      (node (ref "U2") (pin "AB11") (pinfunction "IO_L32N_GCLK28_2_AB11") (pintype "bidirectional"))
    )
    (net (code "177") (name "/~{SPIC_STE}") (class "Default")
      (node (ref "U2") (pin "AA4") (pinfunction "IO_L57P_2_AA4") (pintype "bidirectional"))
    )
    (net (code "178") (name "GND_D") (class "Default")
      (node (ref "R27") (pin "1") (pinfunction "1_1") (pintype "passive"))
      (node (ref "R28") (pin "1") (pinfunction "1_1") (pintype "passive"))
      (node (ref "R56") (pin "1") (pinfunction "1_1") (pintype "passive"))
    )
    (net (code "179") (name "Net-(U2C-IO_L1N_M0_CMPMISO_2)") (class "Default")
      (node (ref "R26") (pin "1") (pinfunction "1_1") (pintype "passive"))
      (node (ref "R56") (pin "2") (pinfunction "2_2") (pintype "passive"))
      (node (ref "U2") (pin "AA22") (pinfunction "IO_L1N_M0_CMPMISO_2_AA22") (pintype "bidirectional"))
    )
    (net (code "180") (name "Net-(U2C-IO_L13P_M1_2)") (class "Default")
      (node (ref "R28") (pin "2") (pinfunction "2_2") (pintype "passive"))
      (node (ref "R57") (pin "1") (pinfunction "1_1") (pintype "passive"))
      (node (ref "U2") (pin "U15") (pinfunction "IO_L13P_M1_2_U15") (pintype "bidirectional"))
    )
    (net (code "181") (name "Net-(U2C-IO_L65P_INIT_B_2)") (class "Default")
      (node (ref "R29") (pin "1") (pinfunction "1_1") (pintype "passive"))
      (node (ref "U2") (pin "T6") (pinfunction "IO_L65P_INIT_B_2_T6") (pintype "bidirectional"))
    )
    (net (code "182") (name "unconnected-(U2A-IO_L2P_0-PadC5)") (class "Default")
      (node (ref "U2") (pin "C5") (pinfunction "IO_L2P_0_C5") (pintype "bidirectional"))
    )
    (net (code "183") (name "unconnected-(U2A-IO_L7P_0-PadD9)") (class "Default")
      (node (ref "U2") (pin "D9") (pinfunction "IO_L7P_0_D9") (pintype "bidirectional"))
    )
    (net (code "184") (name "unconnected-(U2A-IO_L33P_0-PadD10)") (class "Default")
      (node (ref "U2") (pin "D10") (pinfunction "IO_L33P_0_D10") (pintype "bidirectional"))
    )
    (net (code "185") (name "unconnected-(U2A-IO_L35P_GCLK17_0-PadC11)") (class "Default")
      (node (ref "U2") (pin "C11") (pinfunction "IO_L35P_GCLK17_0_C11") (pintype "bidirectional"))
    )
    (net (code "186") (name "unconnected-(U2A-IO_L36N_GCLK14_0-PadC12)") (class "Default")
      (node (ref "U2") (pin "C12") (pinfunction "IO_L36N_GCLK14_0_C12") (pintype "bidirectional"))
    )
    (net (code "187") (name "unconnected-(U2A-IO_L36P_GCLK15_0-PadD11)") (class "Default")
      (node (ref "U2") (pin "D11") (pinfunction "IO_L36P_GCLK15_0_D11") (pintype "bidirectional"))
    )
    (net (code "188") (name "unconnected-(U2A-IO_L43N_0-PadD12)") (class "Default")
      (node (ref "U2") (pin "D12") (pinfunction "IO_L43N_0_D12") (pintype "bidirectional"))
    )
    (net (code "189") (name "unconnected-(U2A-IO_L43P_0-PadE12)") (class "Default")
      (node (ref "U2") (pin "E12") (pinfunction "IO_L43P_0_E12") (pintype "bidirectional"))
    )
    (net (code "190") (name "unconnected-(U2A-IO_L45N_0-PadD13)") (class "Default")
      (node (ref "U2") (pin "D13") (pinfunction "IO_L45N_0_D13") (pintype "bidirectional"))
    )
    (net (code "191") (name "unconnected-(U2A-IO_L45P_0-PadF13)") (class "Default")
      (node (ref "U2") (pin "F13") (pinfunction "IO_L45P_0_F13") (pintype "bidirectional"))
    )
    (net (code "192") (name "unconnected-(U2A-IO_L46N_0-PadG13)") (class "Default")
      (node (ref "U2") (pin "G13") (pinfunction "IO_L46N_0_G13") (pintype "bidirectional"))
    )
    (net (code "193") (name "unconnected-(U2A-IO_L47P_0-PadE14)") (class "Default")
      (node (ref "U2") (pin "E14") (pinfunction "IO_L47P_0_E14") (pintype "bidirectional"))
    )
    (net (code "194") (name "unconnected-(U2A-IO_L62P_0-PadD15)") (class "Default")
      (node (ref "U2") (pin "D15") (pinfunction "IO_L62P_0_D15") (pintype "bidirectional"))
    )
    (net (code "195") (name "unconnected-(U2A-IO_L66P_SCP1_0-PadE16)") (class "Default")
      (node (ref "U2") (pin "E16") (pinfunction "IO_L66P_SCP1_0_E16") (pintype "bidirectional"))
    )
    (net (code "196") (name "unconnected-(U2B-IO_L10P_1-PadF16)") (class "Default")
      (node (ref "U2") (pin "F16") (pinfunction "IO_L10P_1_F16") (pintype "bidirectional+no_connect"))
    )
    (net (code "197") (name "unconnected-(U2B-IO_L21N_1-PadJ16)") (class "Default")
      (node (ref "U2") (pin "J16") (pinfunction "IO_L21N_1_J16") (pintype "bidirectional+no_connect"))
    )
    (net (code "198") (name "unconnected-(U2B-IO_L21P_1-PadK16)") (class "Default")
      (node (ref "U2") (pin "K16") (pinfunction "IO_L21P_1_K16") (pintype "bidirectional+no_connect"))
    )
    (net (code "199") (name "unconnected-(U2B-IO_L28N_VREF_1-PadH17)") (class "Default")
      (node (ref "U2") (pin "H17") (pinfunction "IO_L28N_VREF_1_H17") (pintype "bidirectional+no_connect"))
    )
    (net (code "200") (name "unconnected-(U2B-IO_L30N_A20_M1A11_1-PadF19)") (class "Default")
      (node (ref "U2") (pin "F19") (pinfunction "IO_L30N_A20_M1A11_1_F19") (pintype "bidirectional+no_connect"))
    )
    (net (code "201") (name "unconnected-(U2B-IO_L33P_A15_M1A10_1-PadG19)") (class "Default")
      (node (ref "U2") (pin "G19") (pinfunction "IO_L33P_A15_M1A10_1_G19") (pintype "bidirectional+no_connect"))
    )
    (net (code "202") (name "unconnected-(U2B-IO_L34N_A12_M1BA2_1-PadH18)") (class "Default")
      (node (ref "U2") (pin "H18") (pinfunction "IO_L34N_A12_M1BA2_1_H18") (pintype "bidirectional+no_connect"))
    )
    (net (code "203") (name "unconnected-(U2B-IO_L34P_A13_M1WE_1-PadH19)") (class "Default")
      (node (ref "U2") (pin "H19") (pinfunction "IO_L34P_A13_M1WE_1_H19") (pintype "bidirectional+no_connect"))
    )
    (net (code "204") (name "unconnected-(U2B-IO_L36P_A9_M1BA0_1-PadJ17)") (class "Default")
      (node (ref "U2") (pin "J17") (pinfunction "IO_L36P_A9_M1BA0_1_J17") (pintype "bidirectional+no_connect"))
    )
    (net (code "205") (name "unconnected-(U2B-IO_L38N_A4_M1CLKN_1-PadJ19)") (class "Default")
      (node (ref "U2") (pin "J19") (pinfunction "IO_L38N_A4_M1CLKN_1_J19") (pintype "bidirectional+no_connect"))
    )
    (net (code "206") (name "unconnected-(U2B-IO_L47N_LDC_M1DQ1_1-PadN22)") (class "Default")
      (node (ref "U2") (pin "N22") (pinfunction "IO_L47N_LDC_M1DQ1_1_N22") (pintype "bidirectional+no_connect"))
    )
    (net (code "207") (name "unconnected-(U2B-IO_L47P_FWE_B_M1DQ0_1-PadN20)") (class "Default")
      (node (ref "U2") (pin "N20") (pinfunction "IO_L47P_FWE_B_M1DQ0_1_N20") (pintype "bidirectional+no_connect"))
    )
    (net (code "208") (name "unconnected-(U2B-IO_L48P_HDC_M1DQ8_1-PadP21)") (class "Default")
      (node (ref "U2") (pin "P21") (pinfunction "IO_L48P_HDC_M1DQ8_1_P21") (pintype "bidirectional+no_connect"))
    )
    (net (code "209") (name "unconnected-(U2B-IO_L58N_1-PadL15)") (class "Default")
      (node (ref "U2") (pin "L15") (pinfunction "IO_L58N_1_L15") (pintype "bidirectional+no_connect"))
    )
    (net (code "210") (name "unconnected-(U2B-IO_L61N_1-PadK18)") (class "Default")
      (node (ref "U2") (pin "K18") (pinfunction "IO_L61N_1_K18") (pintype "bidirectional+no_connect"))
    )
    (net (code "211") (name "unconnected-(U2B-IO_L61P_1-PadL17)") (class "Default")
      (node (ref "U2") (pin "L17") (pinfunction "IO_L61P_1_L17") (pintype "bidirectional+no_connect"))
    )
    (net (code "212") (name "unconnected-(U2B-IO_L71P_1-PadM17)") (class "Default")
      (node (ref "U2") (pin "M17") (pinfunction "IO_L71P_1_M17") (pintype "bidirectional+no_connect"))
    )
    (net (code "213") (name "unconnected-(U2B-IO_L73P_1-PadP18)") (class "Default")
      (node (ref "U2") (pin "P18") (pinfunction "IO_L73P_1_P18") (pintype "bidirectional+no_connect"))
    )
    (net (code "214") (name "unconnected-(U2B-IO_L74N_DOUT_BUSY_1-PadT20)") (class "Default")
      (node (ref "U2") (pin "T20") (pinfunction "IO_L74N_DOUT_BUSY_1_T20") (pintype "bidirectional+no_connect"))
    )
    (net (code "215") (name "unconnected-(U2C-IO_L2N_CMPMOSI_2-PadAB21)") (class "Default")
      (node (ref "U2") (pin "AB21") (pinfunction "IO_L2N_CMPMOSI_2_AB21") (pintype "bidirectional"))
    )
    (net (code "216") (name "unconnected-(U2C-IO_L2P_CMPCLK_2-PadAA21)") (class "Default")
      (node (ref "U2") (pin "AA21") (pinfunction "IO_L2P_CMPCLK_2_AA21") (pintype "bidirectional"))
    )
    (net (code "217") (name "unconnected-(U2C-IO_L4N_VREF_2-PadT17)") (class "Default")
      (node (ref "U2") (pin "T17") (pinfunction "IO_L4N_VREF_2_T17") (pintype "bidirectional"))
    )
    (net (code "218") (name "unconnected-(U2C-IO_L4P_2-PadT18)") (class "Default")
      (node (ref "U2") (pin "T18") (pinfunction "IO_L4P_2_T18") (pintype "bidirectional"))
    )
    (net (code "219") (name "unconnected-(U2C-IO_L5P_2-PadY19)") (class "Default")
      (node (ref "U2") (pin "Y19") (pinfunction "IO_L5P_2_Y19") (pintype "bidirectional"))
    )
    (net (code "220") (name "unconnected-(U2C-IO_L12N_D2_MISO3_2-PadU13)") (class "Default")
      (node (ref "U2") (pin "U13") (pinfunction "IO_L12N_D2_MISO3_2_U13") (pintype "bidirectional"))
    )
    (net (code "221") (name "unconnected-(U2C-IO_L12P_D1_MISO2_2-PadU14)") (class "Default")
      (node (ref "U2") (pin "U14") (pinfunction "IO_L12P_D1_MISO2_2_U14") (pintype "bidirectional"))
    )
    (net (code "222") (name "unconnected-(U2C-IO_L13N_D10_2-PadV15)") (class "Default")
      (node (ref "U2") (pin "V15") (pinfunction "IO_L13N_D10_2_V15") (pintype "bidirectional"))
    )
    (net (code "223") (name "unconnected-(U2C-IO_L14P_D11_2-PadAA18)") (class "Default")
      (node (ref "U2") (pin "AA18") (pinfunction "IO_L14P_D11_2_AA18") (pintype "bidirectional"))
    )
    (net (code "224") (name "unconnected-(U2C-IO_L15P_2-PadY17)") (class "Default")
      (node (ref "U2") (pin "Y17") (pinfunction "IO_L15P_2_Y17") (pintype "bidirectional"))
    )
    (net (code "225") (name "unconnected-(U2C-IO_L21P_2-PadY15)") (class "Default")
      (node (ref "U2") (pin "Y15") (pinfunction "IO_L21P_2_Y15") (pintype "bidirectional"))
    )
    (net (code "226") (name "unconnected-(U2C-IO_L29N_GCLK2_2-PadY12)") (class "Default")
      (node (ref "U2") (pin "Y12") (pinfunction "IO_L29N_GCLK2_2_Y12") (pintype "bidirectional"))
    )
    (net (code "227") (name "unconnected-(U2C-IO_L29P_GCLK3_2-PadW12)") (class "Default")
      (node (ref "U2") (pin "W12") (pinfunction "IO_L29P_GCLK3_2_W12") (pintype "bidirectional"))
    )
    (net (code "228") (name "unconnected-(U2C-IO_L30N_GCLK0_USERCCLK_2-PadAB13)") (class "Default")
      (node (ref "U2") (pin "AB13") (pinfunction "IO_L30N_GCLK0_USERCCLK_2_AB13") (pintype "bidirectional"))
    )
    (net (code "229") (name "unconnected-(U2C-IO_L30P_GCLK1_D13_2-PadY13)") (class "Default")
      (node (ref "U2") (pin "Y13") (pinfunction "IO_L30P_GCLK1_D13_2_Y13") (pintype "bidirectional"))
    )
    (net (code "230") (name "unconnected-(U2C-IO_L31N_GCLK30_D15_2-PadAB12)") (class "Default")
      (node (ref "U2") (pin "AB12") (pinfunction "IO_L31N_GCLK30_D15_2_AB12") (pintype "bidirectional"))
    )
    (net (code "231") (name "unconnected-(U2C-IO_L31P_GCLK31_D14_2-PadAA12)") (class "Default")
      (node (ref "U2") (pin "AA12") (pinfunction "IO_L31P_GCLK31_D14_2_AA12") (pintype "bidirectional"))
    )
    (net (code "232") (name "unconnected-(U2C-IO_L32P_GCLK29_2-PadY11)") (class "Default")
      (node (ref "U2") (pin "Y11") (pinfunction "IO_L32P_GCLK29_2_Y11") (pintype "bidirectional"))
    )
    (net (code "233") (name "unconnected-(U2C-IO_L42N_2-PadW11)") (class "Default")
      (node (ref "U2") (pin "W11") (pinfunction "IO_L42N_2_W11") (pintype "bidirectional"))
    )
    (net (code "234") (name "unconnected-(U2C-IO_L42P_2-PadV11)") (class "Default")
      (node (ref "U2") (pin "V11") (pinfunction "IO_L42P_2_V11") (pintype "bidirectional"))
    )
    (net (code "235") (name "unconnected-(U2C-IO_L43P_2-PadY9)") (class "Default")
      (node (ref "U2") (pin "Y9") (pinfunction "IO_L43P_2_Y9") (pintype "bidirectional"))
    )
    (net (code "236") (name "unconnected-(U2C-IO_L48P_D7_2-PadY7)") (class "Default")
      (node (ref "U2") (pin "Y7") (pinfunction "IO_L48P_D7_2_Y7") (pintype "bidirectional"))
    )
    (net (code "237") (name "unconnected-(U2C-IO_L58N_2-PadAB3)") (class "Default")
      (node (ref "U2") (pin "AB3") (pinfunction "IO_L58N_2_AB3") (pintype "bidirectional"))
    )
    (net (code "238") (name "unconnected-(U2C-IO_L58P_2-PadY3)") (class "Default")
      (node (ref "U2") (pin "Y3") (pinfunction "IO_L58P_2_Y3") (pintype "bidirectional"))
    )
    (net (code "239") (name "unconnected-(U2C-IO_L62N_D6_2-PadY4)") (class "Default")
      (node (ref "U2") (pin "Y4") (pinfunction "IO_L62N_D6_2_Y4") (pintype "bidirectional"))
    )
    (net (code "240") (name "unconnected-(U2C-IO_L62P_D5_2-PadW4)") (class "Default")
      (node (ref "U2") (pin "W4") (pinfunction "IO_L62P_D5_2_W4") (pintype "bidirectional"))
    )
    (net (code "241") (name "unconnected-(U2C-IO_L64N_D9_2-PadAB2)") (class "Default")
      (node (ref "U2") (pin "AB2") (pinfunction "IO_L64N_D9_2_AB2") (pintype "bidirectional"))
    )
    (net (code "242") (name "unconnected-(U2C-IO_L64P_D8_2-PadAA2)") (class "Default")
      (node (ref "U2") (pin "AA2") (pinfunction "IO_L64P_D8_2_AA2") (pintype "bidirectional"))
    )
    (net (code "243") (name "unconnected-(U2D-IO_L7N_3-PadP7)") (class "Default")
      (node (ref "U2") (pin "P7") (pinfunction "IO_L7N_3_P7") (pintype "bidirectional"))
    )
    (net (code "244") (name "unconnected-(U2D-IO_L7P_3-PadP8)") (class "Default")
      (node (ref "U2") (pin "P8") (pinfunction "IO_L7P_3_P8") (pintype "bidirectional"))
    )
    (net (code "245") (name "unconnected-(U2D-IO_L8N_3-PadP5)") (class "Default")
      (node (ref "U2") (pin "P5") (pinfunction "IO_L8N_3_P5") (pintype "bidirectional"))
    )
    (net (code "246") (name "unconnected-(U2D-IO_L11N_3-PadN7)") (class "Default")
      (node (ref "U2") (pin "N7") (pinfunction "IO_L11N_3_N7") (pintype "bidirectional"))
    )
    (net (code "247") (name "unconnected-(U2D-IO_L11P_3-PadN6)") (class "Default")
      (node (ref "U2") (pin "N6") (pinfunction "IO_L11P_3_N6") (pintype "bidirectional"))
    )
    (net (code "248") (name "unconnected-(U2D-IO_L23N_3-PadM8)") (class "Default")
      (node (ref "U2") (pin "M8") (pinfunction "IO_L23N_3_M8") (pintype "bidirectional"))
    )
    (net (code "249") (name "unconnected-(U2D-IO_L23P_3-PadM7)") (class "Default")
      (node (ref "U2") (pin "M7") (pinfunction "IO_L23P_3_M7") (pintype "bidirectional"))
    )
    (net (code "250") (name "unconnected-(U2D-IO_L25N_3-PadL6)") (class "Default")
      (node (ref "U2") (pin "L6") (pinfunction "IO_L25N_3_L6") (pintype "bidirectional"))
    )
    (net (code "251") (name "unconnected-(U2D-IO_L25P_3-PadM6)") (class "Default")
      (node (ref "U2") (pin "M6") (pinfunction "IO_L25P_3_M6") (pintype "bidirectional"))
    )
    (net (code "252") (name "unconnected-(U2D-IO_L26N_3-PadN4)") (class "Default")
      (node (ref "U2") (pin "N4") (pinfunction "IO_L26N_3_N4") (pintype "bidirectional"))
    )
    (net (code "253") (name "unconnected-(U2D-IO_L31N_VREF_3-PadM4)") (class "Default")
      (node (ref "U2") (pin "M4") (pinfunction "IO_L31N_VREF_3_M4") (pintype "bidirectional"))
    )
    (net (code "254") (name "unconnected-(U2D-IO_L31P_3-PadM5)") (class "Default")
      (node (ref "U2") (pin "M5") (pinfunction "IO_L31P_3_M5") (pintype "bidirectional"))
    )
    (net (code "255") (name "unconnected-(U2D-IO_L36P_M3DQ8_3-PadP2)") (class "Default")
      (node (ref "U2") (pin "P2") (pinfunction "IO_L36P_M3DQ8_3_P2") (pintype "bidirectional"))
    )
    (net (code "256") (name "unconnected-(U2D-IO_L42N_GCLK24_M3LDM_3-PadL4)") (class "Default")
      (node (ref "U2") (pin "L4") (pinfunction "IO_L42N_GCLK24_M3LDM_3_L4") (pintype "bidirectional"))
    )
    (net (code "257") (name "unconnected-(U2D-IO_L43N_GCLK22_IRDY2_M3CASN_3-PadK4)") (class "Default")
      (node (ref "U2") (pin "K4") (pinfunction "IO_L43N_GCLK22_IRDY2_M3CASN_3_K4") (pintype "bidirectional"))
    )
    (net (code "258") (name "unconnected-(U2D-IO_L43P_GCLK23_M3RASN_3-PadK5)") (class "Default")
      (node (ref "U2") (pin "K5") (pinfunction "IO_L43P_GCLK23_M3RASN_3_K5") (pintype "bidirectional"))
    )
    (net (code "259") (name "unconnected-(U2D-IO_L44N_GCLK20_M3A6_3-PadJ4)") (class "Default")
      (node (ref "U2") (pin "J4") (pinfunction "IO_L44N_GCLK20_M3A6_3_J4") (pintype "bidirectional"))
    )
    (net (code "260") (name "unconnected-(U2D-IO_L45N_M3ODT_3-PadJ6)") (class "Default")
      (node (ref "U2") (pin "J6") (pinfunction "IO_L45N_M3ODT_3_J6") (pintype "bidirectional"))
    )
    (net (code "261") (name "unconnected-(U2D-IO_L45P_M3A3_3-PadK6)") (class "Default")
      (node (ref "U2") (pin "K6") (pinfunction "IO_L45P_M3A3_3_K6") (pintype "bidirectional"))
    )
    (net (code "262") (name "unconnected-(U2D-IO_L46P_M3CLK_3-PadH4)") (class "Default")
      (node (ref "U2") (pin "H4") (pinfunction "IO_L46P_M3CLK_3_H4") (pintype "bidirectional"))
    )
    (net (code "263") (name "unconnected-(U2D-IO_L47N_M3A1_3-PadH1)") (class "Default")
      (node (ref "U2") (pin "H1") (pinfunction "IO_L47N_M3A1_3_H1") (pintype "bidirectional"))
    )
    (net (code "264") (name "unconnected-(U2D-IO_L47P_M3A0_3-PadH2)") (class "Default")
      (node (ref "U2") (pin "H2") (pinfunction "IO_L47P_M3A0_3_H2") (pintype "bidirectional"))
    )
    (net (code "265") (name "unconnected-(U2D-IO_L48N_M3BA1_3-PadG1)") (class "Default")
      (node (ref "U2") (pin "G1") (pinfunction "IO_L48N_M3BA1_3_G1") (pintype "bidirectional"))
    )
    (net (code "266") (name "unconnected-(U2D-IO_L49N_M3A2_3-PadH5)") (class "Default")
      (node (ref "U2") (pin "H5") (pinfunction "IO_L49N_M3A2_3_H5") (pintype "bidirectional"))
    )
    (net (code "267") (name "unconnected-(U2D-IO_L49P_M3A7_3-PadH6)") (class "Default")
      (node (ref "U2") (pin "H6") (pinfunction "IO_L49P_M3A7_3_H6") (pintype "bidirectional"))
    )
    (net (code "268") (name "unconnected-(U2D-IO_L50N_M3BA2_3-PadF1)") (class "Default")
      (node (ref "U2") (pin "F1") (pinfunction "IO_L50N_M3BA2_3_F1") (pintype "bidirectional"))
    )
    (net (code "269") (name "unconnected-(U2D-IO_L50P_M3WE_3-PadF2)") (class "Default")
      (node (ref "U2") (pin "F2") (pinfunction "IO_L50P_M3WE_3_F2") (pintype "bidirectional"))
    )
    (net (code "270") (name "unconnected-(U2D-IO_L51P_M3A10_3-PadG4)") (class "Default")
      (node (ref "U2") (pin "G4") (pinfunction "IO_L51P_M3A10_3_G4") (pintype "bidirectional"))
    )
    (net (code "271") (name "unconnected-(U2D-IO_L52N_M3A9_3-PadE1)") (class "Default")
      (node (ref "U2") (pin "E1") (pinfunction "IO_L52N_M3A9_3_E1") (pintype "bidirectional"))
    )
    (net (code "272") (name "unconnected-(U2D-IO_L52P_M3A8_3-PadE3)") (class "Default")
      (node (ref "U2") (pin "E3") (pinfunction "IO_L52P_M3A8_3_E3") (pintype "bidirectional"))
    )
    (net (code "273") (name "unconnected-(U2D-IO_L53P_M3CKE_3-PadD2)") (class "Default")
      (node (ref "U2") (pin "D2") (pinfunction "IO_L53P_M3CKE_3_D2") (pintype "bidirectional"))
    )
    (net (code "274") (name "unconnected-(U2D-IO_L55N_M3A14_3-PadF5)") (class "Default")
      (node (ref "U2") (pin "F5") (pinfunction "IO_L55N_M3A14_3_F5") (pintype "bidirectional"))
    )
    (net (code "275") (name "unconnected-(U2D-IO_L55P_M3A13_3-PadG6)") (class "Default")
      (node (ref "U2") (pin "G6") (pinfunction "IO_L55P_M3A13_3_G6") (pintype "bidirectional"))
    )
    (net (code "276") (name "unconnected-(U2D-IO_L57N_VREF_3-PadK8)") (class "Default")
      (node (ref "U2") (pin "K8") (pinfunction "IO_L57N_VREF_3_K8") (pintype "bidirectional"))
    )
    (net (code "277") (name "unconnected-(U2D-IO_L57P_3-PadK7)") (class "Default")
      (node (ref "U2") (pin "K7") (pinfunction "IO_L57P_3_K7") (pintype "bidirectional"))
    )
    (net (code "278") (name "unconnected-(U2D-IO_L59N_3-PadH8)") (class "Default")
      (node (ref "U2") (pin "H8") (pinfunction "IO_L59N_3_H8") (pintype "bidirectional"))
    )
    (net (code "279") (name "unconnected-(U2D-IO_L59P_3-PadJ7)") (class "Default")
      (node (ref "U2") (pin "J7") (pinfunction "IO_L59P_3_J7") (pintype "bidirectional"))
    )
    (net (code "280") (name "unconnected-(U2D-IO_L80N_3-PadF7)") (class "Default")
      (node (ref "U2") (pin "F7") (pinfunction "IO_L80N_3_F7") (pintype "bidirectional"))
    )
    (net (code "281") (name "unconnected-(U2D-IO_L80P_3-PadG7)") (class "Default")
      (node (ref "U2") (pin "G7") (pinfunction "IO_L80P_3_G7") (pintype "bidirectional"))
    )
    (net (code "282") (name "unconnected-(U2D-IO_L82N_3-PadE6)") (class "Default")
      (node (ref "U2") (pin "E6") (pinfunction "IO_L82N_3_E6") (pintype "bidirectional"))
    )
  )
)
